# brenner3v3.net
KiCad netlist of a schematic drawn in EAGLE
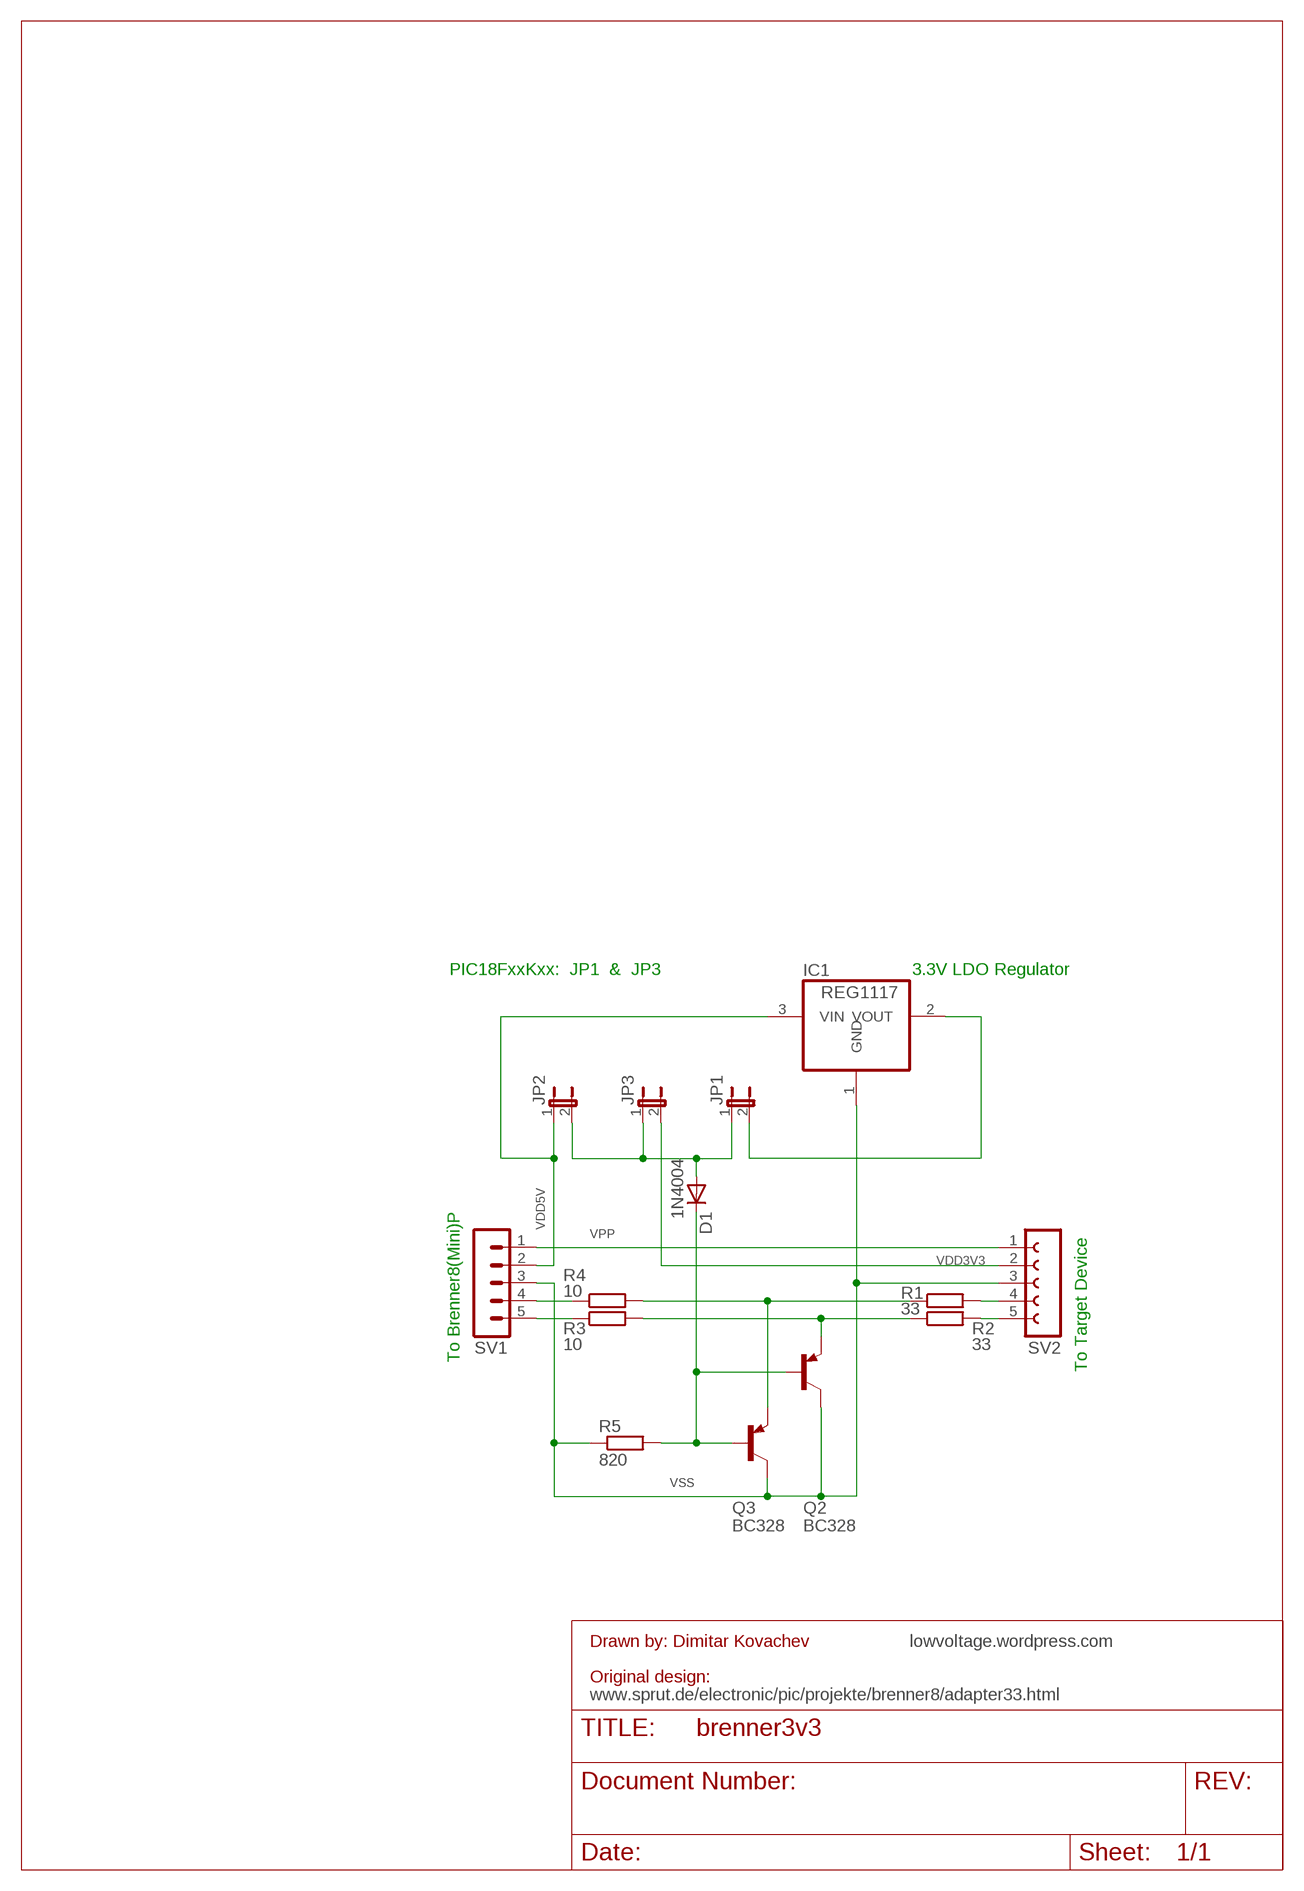
[diagram p0: schematic, sheet 1]

(export (version "E")
  (design (tool "Eeschema 10.0.6"))
  (components
    (comp (ref "D1")
      (value "1N4004")
      (footprint "eagle-import:DO41-10")
      (libsource (lib "eagle-import") (part "1N4004"))
    )
    (comp (ref "IC1")
      (value "REG1117")
      (footprint "eagle-import:SOT223")
      (libsource (lib "eagle-import") (part "REG1117"))
    )
    (comp (ref "JP1")
      (value "JP1E")
      (footprint "eagle-import:JP1")
      (libsource (lib "eagle-import") (part "JP1E"))
    )
    (comp (ref "JP2")
      (value "JP1E")
      (footprint "eagle-import:JP1")
      (libsource (lib "eagle-import") (part "JP1E"))
    )
    (comp (ref "JP3")
      (value "JP1E")
      (footprint "eagle-import:JP1")
      (libsource (lib "eagle-import") (part "JP1E"))
    )
    (comp (ref "Q2")
      (value "BC328")
      (footprint "eagle-import:TO92-EBC")
      (libsource (lib "eagle-import") (part "-PNP-TO92-EBCBC328-25"))
    )
    (comp (ref "Q3")
      (value "BC328")
      (footprint "eagle-import:TO92-EBC")
      (libsource (lib "eagle-import") (part "-PNP-TO92-EBCBC328-25"))
    )
    (comp (ref "R1")
      (value "33")
      (footprint "eagle-import:0207_10")
      (libsource (lib "eagle-import") (part "R-EU_0207/10"))
    )
    (comp (ref "R2")
      (value "33")
      (footprint "eagle-import:0207_10")
      (libsource (lib "eagle-import") (part "R-EU_0207/10"))
    )
    (comp (ref "R3")
      (value "10")
      (footprint "eagle-import:0207_10")
      (libsource (lib "eagle-import") (part "R-EU_0207/10"))
    )
    (comp (ref "R4")
      (value "10")
      (footprint "eagle-import:0207_10")
      (libsource (lib "eagle-import") (part "R-EU_0207/10"))
    )
    (comp (ref "R5")
      (value "820")
      (footprint "eagle-import:0207_2V")
      (libsource (lib "eagle-import") (part "R-EU_0207/2V"))
    )
    (comp (ref "SV1")
      (value "MA05-1")
      (footprint "eagle-import:MA05-1")
      (libsource (lib "eagle-import") (part "MA05-1"))
    )
    (comp (ref "SV2")
      (value "FE05-1")
      (footprint "eagle-import:FE05-1")
      (libsource (lib "eagle-import") (part "FE05-1"))
    )
  )
  (nets
    (net (code "1") (name "/VDD3V3") (class "Default")
      (node (ref "JP3") (pin "2") (pinfunction "2_2") (pintype "passive"))
      (node (ref "SV2") (pin "2") (pinfunction "2_2") (pintype "passive"))
    )
    (net (code "2") (name "/VDD5V") (class "Default")
      (node (ref "IC1") (pin "3") (pinfunction "VIN_3") (pintype "input"))
      (node (ref "JP2") (pin "1") (pinfunction "1_1") (pintype "passive"))
      (node (ref "SV1") (pin "2") (pinfunction "2_2") (pintype "passive"))
    )
    (net (code "3") (name "/VPP") (class "Default")
      (node (ref "SV1") (pin "1") (pinfunction "1_1") (pintype "passive"))
      (node (ref "SV2") (pin "1") (pinfunction "1_1") (pintype "passive"))
    )
    (net (code "4") (name "/VSS") (class "Default")
      (node (ref "IC1") (pin "1") (pinfunction "GND_1") (pintype "power_in"))
      (node (ref "Q2") (pin "C") (pinfunction "C_C") (pintype "passive"))
      (node (ref "Q3") (pin "C") (pinfunction "C_C") (pintype "passive"))
      (node (ref "R5") (pin "1") (pinfunction "1_1") (pintype "passive"))
      (node (ref "SV1") (pin "3") (pinfunction "3_3") (pintype "passive"))
      (node (ref "SV2") (pin "3") (pinfunction "3_3") (pintype "passive"))
    )
    (net (code "5") (name "Net-(D1-PadA)") (class "Default")
      (node (ref "D1") (pin "A") (pinfunction "A_A") (pintype "passive"))
      (node (ref "JP1") (pin "1") (pinfunction "1_1") (pintype "passive"))
      (node (ref "JP2") (pin "2") (pinfunction "2_2") (pintype "passive"))
      (node (ref "JP3") (pin "1") (pinfunction "1_1") (pintype "passive"))
    )
    (net (code "6") (name "Net-(D1-PadC)") (class "Default")
      (node (ref "D1") (pin "C") (pinfunction "C_C") (pintype "passive"))
      (node (ref "Q2") (pin "B") (pinfunction "B_B") (pintype "passive"))
      (node (ref "Q3") (pin "B") (pinfunction "B_B") (pintype "passive"))
      (node (ref "R5") (pin "2") (pinfunction "2_2") (pintype "passive"))
    )
    (net (code "7") (name "Net-(IC1-VOUT)") (class "Default")
      (node (ref "IC1") (pin "2") (pinfunction "VOUT_2") (pintype "output"))
      (node (ref "JP1") (pin "2") (pinfunction "2_2") (pintype "passive"))
    )
    (net (code "8") (name "Net-(Q2-PadE)") (class "Default")
      (node (ref "Q2") (pin "E") (pinfunction "E_E") (pintype "passive"))
      (node (ref "R2") (pin "1") (pinfunction "1_1") (pintype "passive"))
      (node (ref "R3") (pin "2") (pinfunction "2_2") (pintype "passive"))
    )
    (net (code "9") (name "Net-(Q3-PadE)") (class "Default")
      (node (ref "Q3") (pin "E") (pinfunction "E_E") (pintype "passive"))
      (node (ref "R1") (pin "1") (pinfunction "1_1") (pintype "passive"))
      (node (ref "R4") (pin "2") (pinfunction "2_2") (pintype "passive"))
    )
    (net (code "10") (name "Net-(R1-Pad2)") (class "Default")
      (node (ref "R1") (pin "2") (pinfunction "2_2") (pintype "passive"))
      (node (ref "SV2") (pin "4") (pinfunction "4_4") (pintype "passive"))
    )
    (net (code "11") (name "Net-(R2-Pad2)") (class "Default")
      (node (ref "R2") (pin "2") (pinfunction "2_2") (pintype "passive"))
      (node (ref "SV2") (pin "5") (pinfunction "5_5") (pintype "passive"))
    )
    (net (code "12") (name "Net-(R3-Pad1)") (class "Default")
      (node (ref "R3") (pin "1") (pinfunction "1_1") (pintype "passive"))
      (node (ref "SV1") (pin "5") (pinfunction "5_5") (pintype "passive"))
    )
    (net (code "13") (name "Net-(R4-Pad1)") (class "Default")
      (node (ref "R4") (pin "1") (pinfunction "1_1") (pintype "passive"))
      (node (ref "SV1") (pin "4") (pinfunction "4_4") (pintype "passive"))
    )
  )
)
